# Processor.net
KiCad netlist of a schematic drawn in Altium Designer
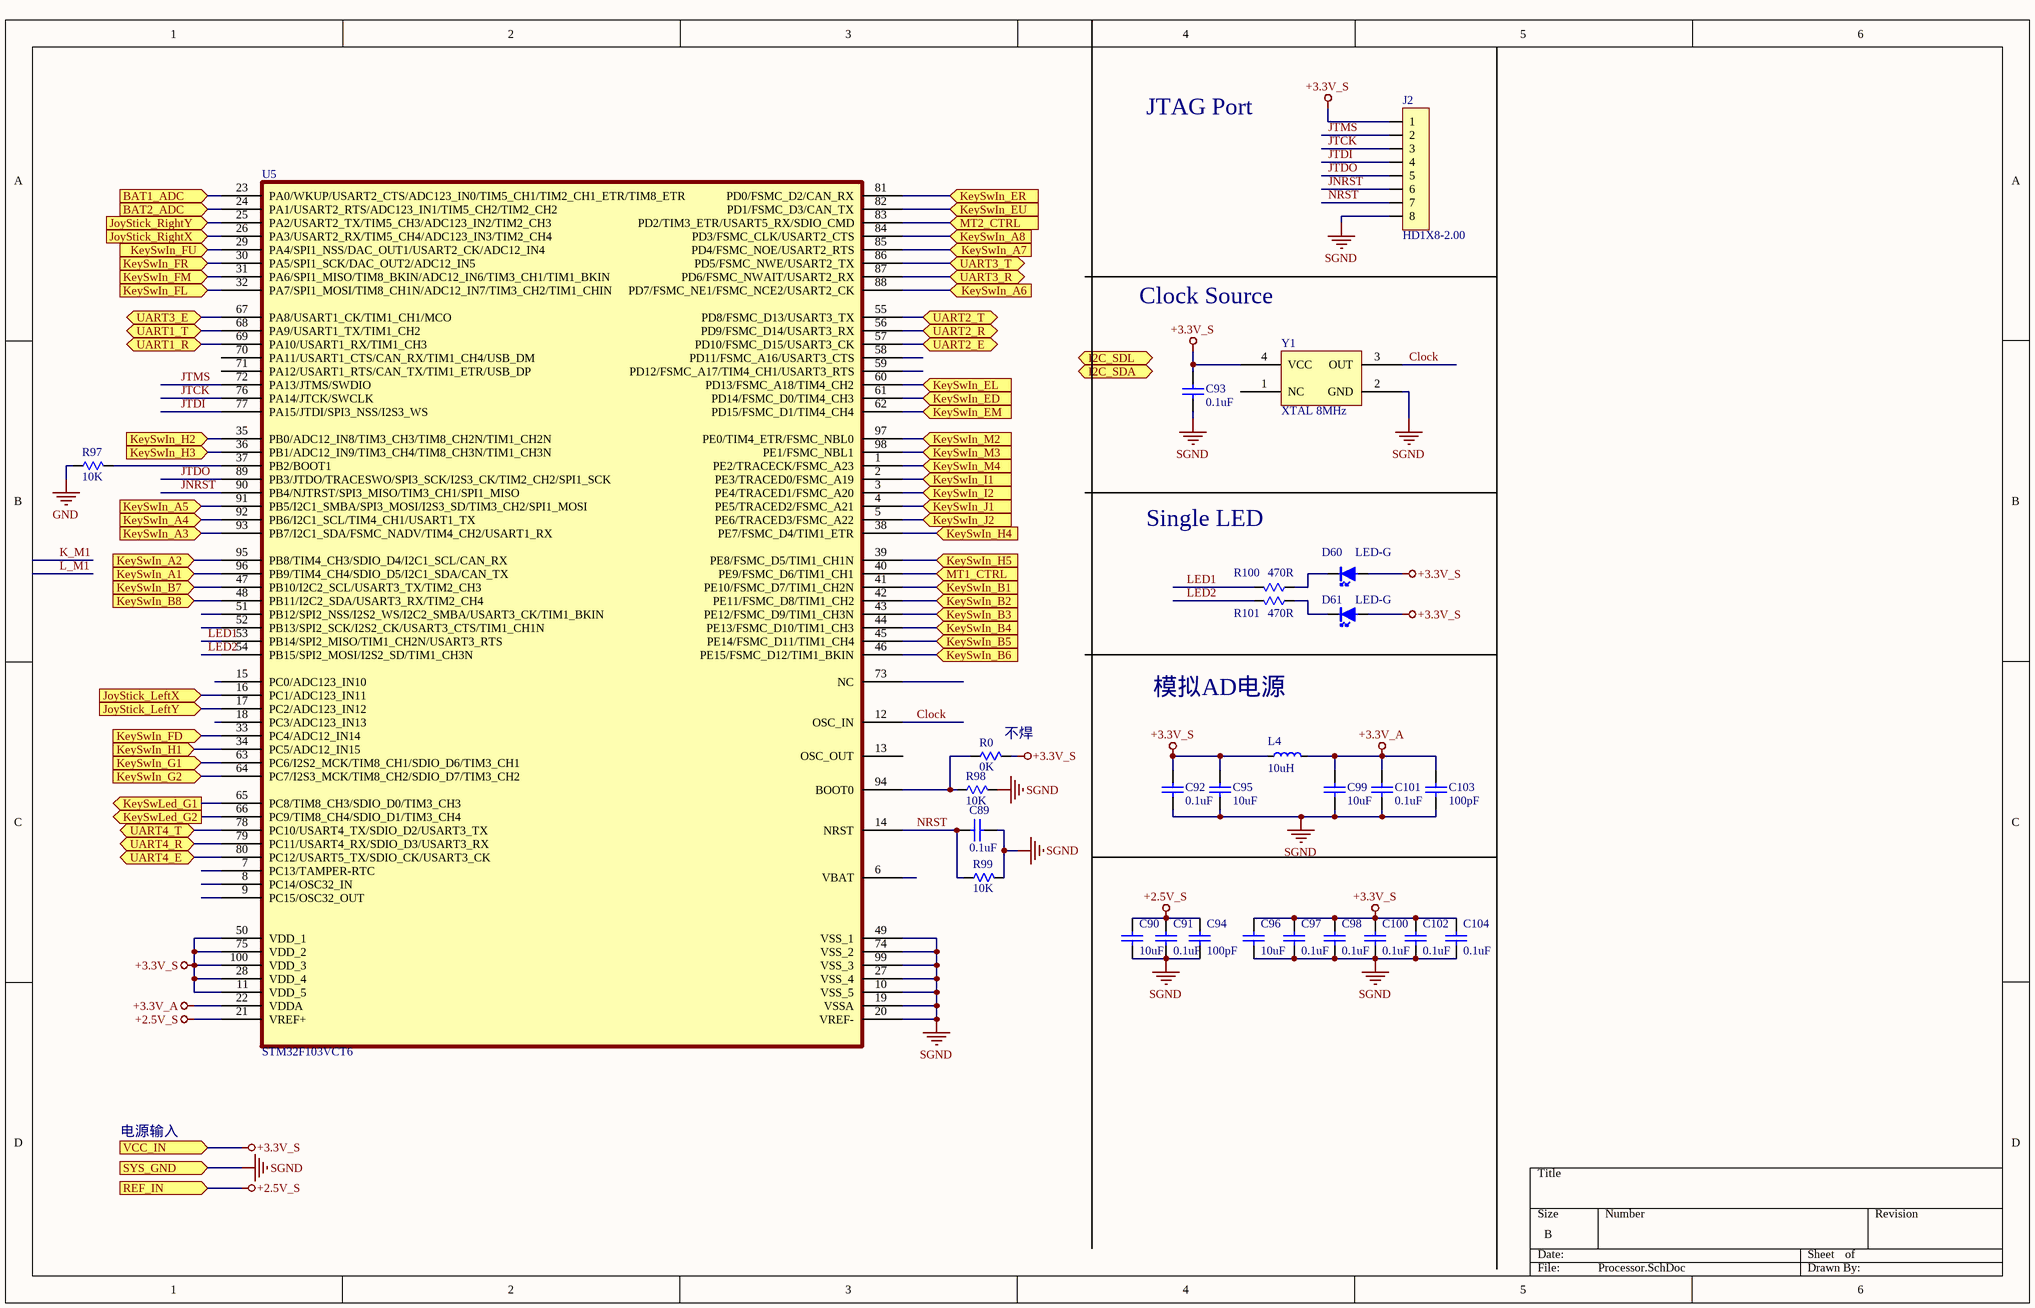
[diagram p0: Processor.SchDoc]

(export (version "E")
  (design (tool "Eeschema 10.0.6"))
  (components
    (comp (ref "C89")
      (value "0.1uF")
      (footprint "C0603")
      (description "CAP")
      (fields (field (name "PUBLISHER") "Altium Limited"))
      (libsource (lib "Passive Components Class") (part "CAP"))
    )
    (comp (ref "C90")
      (value "10uF")
      (footprint "C0805")
      (description "CAP")
      (fields (field (name "PUBLISHER") "Altium Limited"))
      (libsource (lib "Passive Components Class") (part "CAP"))
    )
    (comp (ref "C91")
      (value "0.1uF")
      (footprint "C0603")
      (description "CAP")
      (fields (field (name "PUBLISHER") "Altium Limited"))
      (libsource (lib "Passive Components Class") (part "CAP"))
    )
    (comp (ref "C92")
      (value "0.1uF")
      (footprint "C0603")
      (description "CAP")
      (fields (field (name "PUBLISHER") "Altium Limited"))
      (libsource (lib "Passive Components Class") (part "CAP"))
    )
    (comp (ref "C93")
      (value "0.1uF")
      (footprint "C0603")
      (description "Capacitor")
      (fields (field (name "PUBLISHER") "Altium Limited"))
      (libsource (lib "Miscellaneous Devices") (part "Cap"))
    )
    (comp (ref "C94")
      (value "100pF")
      (footprint "C0603")
      (description "CAP")
      (fields (field (name "PUBLISHER") "Altium Limited"))
      (libsource (lib "Passive Components Class") (part "CAP"))
    )
    (comp (ref "C95")
      (value "10uF")
      (footprint "C0805")
      (description "CAP")
      (fields (field (name "PUBLISHER") "Altium Limited"))
      (libsource (lib "Passive Components Class") (part "CAP"))
    )
    (comp (ref "C96")
      (value "10uF")
      (footprint "C0805")
      (description "CAP")
      (fields (field (name "PUBLISHER") "Altium Limited"))
      (libsource (lib "Passive Components Class") (part "CAP"))
    )
    (comp (ref "C97")
      (value "0.1uF")
      (footprint "C0603")
      (description "CAP")
      (fields (field (name "PUBLISHER") "Altium Limited"))
      (libsource (lib "Passive Components Class") (part "CAP"))
    )
    (comp (ref "C98")
      (value "0.1uF")
      (footprint "C0603")
      (description "CAP")
      (fields (field (name "PUBLISHER") "Altium Limited"))
      (libsource (lib "Passive Components Class") (part "CAP"))
    )
    (comp (ref "C99")
      (value "10uF")
      (footprint "C0805")
      (description "CAP")
      (fields (field (name "PUBLISHER") "Altium Limited"))
      (libsource (lib "Passive Components Class") (part "CAP"))
    )
    (comp (ref "C100")
      (value "0.1uF")
      (footprint "C0603")
      (description "CAP")
      (fields (field (name "PUBLISHER") "Altium Limited"))
      (libsource (lib "Passive Components Class") (part "CAP"))
    )
    (comp (ref "C101")
      (value "0.1uF")
      (footprint "C0603")
      (description "CAP")
      (fields (field (name "PUBLISHER") "Altium Limited"))
      (libsource (lib "Passive Components Class") (part "CAP"))
    )
    (comp (ref "C102")
      (value "0.1uF")
      (footprint "C0603")
      (description "CAP")
      (fields (field (name "PUBLISHER") "Altium Limited"))
      (libsource (lib "Passive Components Class") (part "CAP"))
    )
    (comp (ref "C103")
      (value "100pF")
      (footprint "C0603")
      (description "CAP")
      (fields (field (name "PUBLISHER") "Altium Limited"))
      (libsource (lib "Passive Components Class") (part "CAP"))
    )
    (comp (ref "C104")
      (value "0.1uF")
      (footprint "C0603")
      (description "CAP")
      (fields (field (name "PUBLISHER") "Altium Limited"))
      (libsource (lib "Passive Components Class") (part "CAP"))
    )
    (comp (ref "D60")
      (value "LED-G")
      (footprint "LED0805")
      (libsource (lib "Passive Components Class") (part "LED"))
    )
    (comp (ref "D61")
      (value "LED-G")
      (footprint "LED0805")
      (libsource (lib "Passive Components Class") (part "LED"))
    )
    (comp (ref "J2")
      (value "HD1X8-2.00")
      (footprint "SHD1X8-2.00")
      (libsource (lib "Connector Class") (part "HEADER1X8"))
    )
    (comp (ref "L4")
      (value "10uH")
      (footprint "L0603-C")
      (description "INDUCTOR")
      (fields (field (name "PUBLISHER") "Altium Limited"))
      (libsource (lib "Passive Components Class") (part "INDUCTOR"))
    )
    (comp (ref "R0")
      (value "0K")
      (footprint "R0603")
      (description "Resistor")
      (fields (field (name "PUBLISHER") "Altium Limited"))
      (libsource (lib "UP-Robot") (part "Res"))
    )
    (comp (ref "R97")
      (value "10K")
      (footprint "R0603")
      (description "Resistor")
      (fields (field (name "PUBLISHER") "Altium Limited"))
      (libsource (lib "UP-Robot") (part "Res"))
    )
    (comp (ref "R98")
      (value "10K")
      (footprint "R0603")
      (description "Resistor")
      (fields (field (name "PUBLISHER") "Altium Limited"))
      (libsource (lib "UP-Robot") (part "Res"))
    )
    (comp (ref "R99")
      (value "10K")
      (footprint "R0603")
      (description "Resistor")
      (fields (field (name "PUBLISHER") "Altium Limited"))
      (libsource (lib "UP-Robot") (part "Res"))
    )
    (comp (ref "R100")
      (value "470R")
      (footprint "R0805")
      (description "Resistor")
      (fields (field (name "PUBLISHER") "Altium Limited"))
      (libsource (lib "UP-Robot") (part "Res"))
    )
    (comp (ref "R101")
      (value "470R")
      (footprint "R0805")
      (description "Resistor")
      (fields (field (name "PUBLISHER") "Altium Limited"))
      (libsource (lib "UP-Robot") (part "Res"))
    )
    (comp (ref "U5")
      (value "STM32F103VCT6")
      (footprint "STM32F103VCT6")
      (libsource (lib "Microcontrollers Class") (part "STM32F103VCT6"))
    )
    (comp (ref "Y1")
      (value "XTAL 8MHz")
      (footprint "XTAL 5.0X7.0-SM")
      (libsource (lib "Mic2805") (part "XTAL"))
    )
  )
  (nets
    (net (code "1") (name "+2.5V_S") (class "Default")
      (node (ref "C90") (pin "1") (pinfunction "1_1") (pintype "passive"))
      (node (ref "C91") (pin "1") (pinfunction "1_1") (pintype "passive"))
      (node (ref "C94") (pin "1") (pinfunction "1_1") (pintype "passive"))
      (node (ref "U5") (pin "21") (pinfunction "VREF+_21") (pintype "passive"))
    )
    (net (code "2") (name "+3.3V_A") (class "Default")
      (node (ref "C101") (pin "2") (pinfunction "2_2") (pintype "passive"))
      (node (ref "C103") (pin "2") (pinfunction "2_2") (pintype "passive"))
      (node (ref "C99") (pin "2") (pinfunction "2_2") (pintype "passive"))
      (node (ref "L4") (pin "2") (pinfunction "2_2") (pintype "passive"))
      (node (ref "U5") (pin "22") (pinfunction "VDDA_22") (pintype "passive"))
    )
    (net (code "3") (name "+3.3V_S") (class "Default")
      (node (ref "C100") (pin "1") (pinfunction "1_1") (pintype "passive"))
      (node (ref "C102") (pin "1") (pinfunction "1_1") (pintype "passive"))
      (node (ref "C104") (pin "1") (pinfunction "1_1") (pintype "passive"))
      (node (ref "C92") (pin "2") (pinfunction "2_2") (pintype "passive"))
      (node (ref "C93") (pin "2") (pinfunction "2_2") (pintype "passive"))
      (node (ref "C95") (pin "2") (pinfunction "2_2") (pintype "passive"))
      (node (ref "C96") (pin "1") (pinfunction "1_1") (pintype "passive"))
      (node (ref "C97") (pin "1") (pinfunction "1_1") (pintype "passive"))
      (node (ref "C98") (pin "1") (pinfunction "1_1") (pintype "passive"))
      (node (ref "D60") (pin "1") (pinfunction "A_1") (pintype "passive"))
      (node (ref "D61") (pin "1") (pinfunction "A_1") (pintype "passive"))
      (node (ref "J2") (pin "1") (pinfunction "1_1") (pintype "passive"))
      (node (ref "L4") (pin "1") (pinfunction "1_1") (pintype "passive"))
      (node (ref "R0") (pin "1") (pinfunction "1_1") (pintype "passive"))
      (node (ref "U5") (pin "100") (pinfunction "VDD_3_100") (pintype "passive"))
      (node (ref "U5") (pin "11") (pinfunction "VDD_5_11") (pintype "passive"))
      (node (ref "U5") (pin "28") (pinfunction "VDD_4_28") (pintype "passive"))
      (node (ref "U5") (pin "50") (pinfunction "VDD_1_50") (pintype "passive"))
      (node (ref "U5") (pin "75") (pinfunction "VDD_2_75") (pintype "passive"))
      (node (ref "Y1") (pin "4") (pinfunction "VCC_4") (pintype "passive"))
    )
    (net (code "4") (name "/BAT1_ADC") (class "Default")
      (node (ref "U5") (pin "23") (pinfunction "PA0/WKUP/USART2_CTS/ADC123_IN0/TIM5_CH1/TIM2_CH1_ETR/TIM8_ETR_23") (pintype "passive"))
    )
    (net (code "5") (name "/BAT2_ADC") (class "Default")
      (node (ref "U5") (pin "24") (pinfunction "PA1/USART2_RTS/ADC123_IN1/TIM5_CH2/TIM2_CH2_24") (pintype "passive"))
    )
    (net (code "6") (name "/Clock") (class "Default")
      (node (ref "U5") (pin "12") (pinfunction "OSC_IN_12") (pintype "passive"))
      (node (ref "Y1") (pin "3") (pinfunction "OUT_3") (pintype "passive"))
    )
    (net (code "9") (name "/JNRST") (class "Default")
      (node (ref "J2") (pin "6") (pinfunction "6_6") (pintype "passive"))
      (node (ref "U5") (pin "90") (pinfunction "PB4/NJTRST/SPI3_MISO/TIM3_CH1/SPI1_MISO_90") (pintype "passive"))
    )
    (net (code "10") (name "/JTCK") (class "Default")
      (node (ref "J2") (pin "3") (pinfunction "3_3") (pintype "passive"))
      (node (ref "U5") (pin "76") (pinfunction "PA14/JTCK/SWCLK_76") (pintype "passive"))
    )
    (net (code "11") (name "/JTDI") (class "Default")
      (node (ref "J2") (pin "4") (pinfunction "4_4") (pintype "passive"))
      (node (ref "U5") (pin "77") (pinfunction "PA15/JTDI/SPI3_NSS/I2S3_WS_77") (pintype "passive"))
    )
    (net (code "12") (name "/JTDO") (class "Default")
      (node (ref "J2") (pin "5") (pinfunction "5_5") (pintype "passive"))
      (node (ref "U5") (pin "89") (pinfunction "PB3/JTDO/TRACESWO/SPI3_SCK/I2S3_CK/TIM2_CH2/SPI1_SCK_89") (pintype "passive"))
    )
    (net (code "13") (name "/JTMS") (class "Default")
      (node (ref "J2") (pin "2") (pinfunction "2_2") (pintype "passive"))
      (node (ref "U5") (pin "72") (pinfunction "PA13/JTMS/SWDIO_72") (pintype "passive"))
    )
    (net (code "14") (name "/JoyStick_LeftX") (class "Default")
      (node (ref "U5") (pin "16") (pinfunction "PC1/ADC123_IN11_16") (pintype "passive"))
    )
    (net (code "15") (name "/JoyStick_LeftY") (class "Default")
      (node (ref "U5") (pin "17") (pinfunction "PC2/ADC123_IN12_17") (pintype "passive"))
    )
    (net (code "16") (name "/JoyStick_RightX") (class "Default")
      (node (ref "U5") (pin "26") (pinfunction "PA3/USART2_RX/TIM5_CH4/ADC123_IN3/TIM2_CH4_26") (pintype "passive"))
    )
    (net (code "17") (name "/JoyStick_RightY") (class "Default")
      (node (ref "U5") (pin "25") (pinfunction "PA2/USART2_TX/TIM5_CH3/ADC123_IN2/TIM2_CH3_25") (pintype "passive"))
    )
    (net (code "19") (name "/KeySwIn_A1") (class "Default")
      (node (ref "U5") (pin "96") (pinfunction "PB9/TIM4_CH4/SDIO_D5/I2C1_SDA/CAN_TX_96") (pintype "passive"))
    )
    (net (code "20") (name "/KeySwIn_A2") (class "Default")
      (node (ref "U5") (pin "95") (pinfunction "PB8/TIM4_CH3/SDIO_D4/I2C1_SCL/CAN_RX_95") (pintype "passive"))
    )
    (net (code "21") (name "/KeySwIn_A3") (class "Default")
      (node (ref "U5") (pin "93") (pinfunction "PB7/I2C1_SDA/FSMC_NADV/TIM4_CH2/USART1_RX_93") (pintype "passive"))
    )
    (net (code "22") (name "/KeySwIn_A4") (class "Default")
      (node (ref "U5") (pin "92") (pinfunction "PB6/I2C1_SCL/TIM4_CH1/USART1_TX_92") (pintype "passive"))
    )
    (net (code "23") (name "/KeySwIn_A5") (class "Default")
      (node (ref "U5") (pin "91") (pinfunction "PB5/I2C1_SMBA/SPI3_MOSI/I2S3_SD/TIM3_CH2/SPI1_MOSI_91") (pintype "passive"))
    )
    (net (code "24") (name "/KeySwIn_A6") (class "Default")
      (node (ref "U5") (pin "88") (pinfunction "PD7/FSMC_NE1/FSMC_NCE2/USART2_CK_88") (pintype "passive"))
    )
    (net (code "25") (name "/KeySwIn_A7") (class "Default")
      (node (ref "U5") (pin "85") (pinfunction "PD4/FSMC_NOE/USART2_RTS_85") (pintype "passive"))
    )
    (net (code "26") (name "/KeySwIn_A8") (class "Default")
      (node (ref "U5") (pin "84") (pinfunction "PD3/FSMC_CLK/USART2_CTS_84") (pintype "passive"))
    )
    (net (code "27") (name "/KeySwIn_B1") (class "Default")
      (node (ref "U5") (pin "41") (pinfunction "PE10/FSMC_D7/TIM1_CH2N_41") (pintype "passive"))
    )
    (net (code "28") (name "/KeySwIn_B2") (class "Default")
      (node (ref "U5") (pin "42") (pinfunction "PE11/FSMC_D8/TIM1_CH2_42") (pintype "passive"))
    )
    (net (code "29") (name "/KeySwIn_B3") (class "Default")
      (node (ref "U5") (pin "43") (pinfunction "PE12/FSMC_D9/TIM1_CH3N_43") (pintype "passive"))
    )
    (net (code "30") (name "/KeySwIn_B4") (class "Default")
      (node (ref "U5") (pin "44") (pinfunction "PE13/FSMC_D10/TIM1_CH3_44") (pintype "passive"))
    )
    (net (code "31") (name "/KeySwIn_B5") (class "Default")
      (node (ref "U5") (pin "45") (pinfunction "PE14/FSMC_D11/TIM1_CH4_45") (pintype "passive"))
    )
    (net (code "32") (name "/KeySwIn_B6") (class "Default")
      (node (ref "U5") (pin "46") (pinfunction "PE15/FSMC_D12/TIM1_BKIN_46") (pintype "passive"))
    )
    (net (code "33") (name "/KeySwIn_B7") (class "Default")
      (node (ref "U5") (pin "47") (pinfunction "PB10/I2C2_SCL/USART3_TX/TIM2_CH3_47") (pintype "passive"))
    )
    (net (code "34") (name "/KeySwIn_B8") (class "Default")
      (node (ref "U5") (pin "48") (pinfunction "PB11/I2C2_SDA/USART3_RX/TIM2_CH4_48") (pintype "passive"))
    )
    (net (code "35") (name "/KeySwIn_ED") (class "Default")
      (node (ref "U5") (pin "61") (pinfunction "PD14/FSMC_D0/TIM4_CH3_61") (pintype "passive"))
    )
    (net (code "36") (name "/KeySwIn_EL") (class "Default")
      (node (ref "U5") (pin "60") (pinfunction "PD13/FSMC_A18/TIM4_CH2_60") (pintype "passive"))
    )
    (net (code "37") (name "/KeySwIn_EM") (class "Default")
      (node (ref "U5") (pin "62") (pinfunction "PD15/FSMC_D1/TIM4_CH4_62") (pintype "passive"))
    )
    (net (code "38") (name "/KeySwIn_ER") (class "Default")
      (node (ref "U5") (pin "81") (pinfunction "PD0/FSMC_D2/CAN_RX_81") (pintype "passive"))
    )
    (net (code "39") (name "/KeySwIn_EU") (class "Default")
      (node (ref "U5") (pin "82") (pinfunction "PD1/FSMC_D3/CAN_TX_82") (pintype "passive"))
    )
    (net (code "40") (name "/KeySwIn_FD") (class "Default")
      (node (ref "U5") (pin "33") (pinfunction "PC4/ADC12_IN14_33") (pintype "passive"))
    )
    (net (code "41") (name "/KeySwIn_FL") (class "Default")
      (node (ref "U5") (pin "32") (pinfunction "PA7/SPI1_MOSI/TIM8_CH1N/ADC12_IN7/TIM3_CH2/TIM1_CHIN_32") (pintype "passive"))
    )
    (net (code "42") (name "/KeySwIn_FM") (class "Default")
      (node (ref "U5") (pin "31") (pinfunction "PA6/SPI1_MISO/TIM8_BKIN/ADC12_IN6/TIM3_CH1/TIM1_BKIN_31") (pintype "passive"))
    )
    (net (code "43") (name "/KeySwIn_FR") (class "Default")
      (node (ref "U5") (pin "30") (pinfunction "PA5/SPI1_SCK/DAC_OUT2/ADC12_IN5_30") (pintype "passive"))
    )
    (net (code "44") (name "/KeySwIn_FU") (class "Default")
      (node (ref "U5") (pin "29") (pinfunction "PA4/SPI1_NSS/DAC_OUT1/USART2_CK/ADC12_IN4_29") (pintype "passive"))
    )
    (net (code "45") (name "/KeySwIn_G1") (class "Default")
      (node (ref "U5") (pin "63") (pinfunction "PC6/I2S2_MCK/TIM8_CH1/SDIO_D6/TIM3_CH1_63") (pintype "passive"))
    )
    (net (code "46") (name "/KeySwIn_G2") (class "Default")
      (node (ref "U5") (pin "64") (pinfunction "PC7/I2S3_MCK/TIM8_CH2/SDIO_D7/TIM3_CH2_64") (pintype "passive"))
    )
    (net (code "47") (name "/KeySwIn_H1") (class "Default")
      (node (ref "U5") (pin "34") (pinfunction "PC5/ADC12_IN15_34") (pintype "passive"))
    )
    (net (code "48") (name "/KeySwIn_H2") (class "Default")
      (node (ref "U5") (pin "35") (pinfunction "PB0/ADC12_IN8/TIM3_CH3/TIM8_CH2N/TIM1_CH2N_35") (pintype "passive"))
    )
    (net (code "49") (name "/KeySwIn_H3") (class "Default")
      (node (ref "U5") (pin "36") (pinfunction "PB1/ADC12_IN9/TIM3_CH4/TIM8_CH3N/TIM1_CH3N_36") (pintype "passive"))
    )
    (net (code "50") (name "/KeySwIn_H4") (class "Default")
      (node (ref "U5") (pin "38") (pinfunction "PE7/FSMC_D4/TIM1_ETR_38") (pintype "passive"))
    )
    (net (code "51") (name "/KeySwIn_H5") (class "Default")
      (node (ref "U5") (pin "39") (pinfunction "PE8/FSMC_D5/TIM1_CH1N_39") (pintype "passive"))
    )
    (net (code "52") (name "/KeySwIn_I1") (class "Default")
      (node (ref "U5") (pin "2") (pinfunction "PE3/TRACED0/FSMC_A19_2") (pintype "passive"))
    )
    (net (code "53") (name "/KeySwIn_I2") (class "Default")
      (node (ref "U5") (pin "3") (pinfunction "PE4/TRACED1/FSMC_A20_3") (pintype "passive"))
    )
    (net (code "54") (name "/KeySwIn_J1") (class "Default")
      (node (ref "U5") (pin "4") (pinfunction "PE5/TRACED2/FSMC_A21_4") (pintype "passive"))
    )
    (net (code "55") (name "/KeySwIn_J2") (class "Default")
      (node (ref "U5") (pin "5") (pinfunction "PE6/TRACED3/FSMC_A22_5") (pintype "passive"))
    )
    (net (code "56") (name "/KeySwIn_M2") (class "Default")
      (node (ref "U5") (pin "97") (pinfunction "PE0/TIM4_ETR/FSMC_NBL0_97") (pintype "passive"))
    )
    (net (code "57") (name "/KeySwIn_M3") (class "Default")
      (node (ref "U5") (pin "98") (pinfunction "PE1/FSMC_NBL1_98") (pintype "passive"))
    )
    (net (code "58") (name "/KeySwIn_M4") (class "Default")
      (node (ref "U5") (pin "1") (pinfunction "PE2/TRACECK/FSMC_A23_1") (pintype "passive"))
    )
    (net (code "59") (name "/KeySwLed_G1") (class "Default")
      (node (ref "U5") (pin "65") (pinfunction "PC8/TIM8_CH3/SDIO_D0/TIM3_CH3_65") (pintype "passive"))
    )
    (net (code "60") (name "/KeySwLed_G2") (class "Default")
      (node (ref "U5") (pin "66") (pinfunction "PC9/TIM8_CH4/SDIO_D1/TIM3_CH4_66") (pintype "passive"))
    )
    (net (code "61") (name "/LED1") (class "Default")
      (node (ref "R100") (pin "1") (pinfunction "1_1") (pintype "passive"))
      (node (ref "U5") (pin "53") (pinfunction "PB14/SPI2_MISO/TIM1_CH2N/USART3_RTS_53") (pintype "passive"))
    )
    (net (code "62") (name "/LED2") (class "Default")
      (node (ref "R101") (pin "1") (pinfunction "1_1") (pintype "passive"))
      (node (ref "U5") (pin "54") (pinfunction "PB15/SPI2_MOSI/I2S2_SD/TIM1_CH3N_54") (pintype "passive"))
    )
    (net (code "64") (name "/MT1_CTRL") (class "Default")
      (node (ref "U5") (pin "40") (pinfunction "PE9/FSMC_D6/TIM1_CH1_40") (pintype "passive"))
    )
    (net (code "65") (name "/MT2_CTRL") (class "Default")
      (node (ref "U5") (pin "83") (pinfunction "PD2/TIM3_ETR/USART5_RX/SDIO_CMD_83") (pintype "passive"))
    )
    (net (code "66") (name "/NRST") (class "Default")
      (node (ref "C89") (pin "1") (pinfunction "1_1") (pintype "passive"))
      (node (ref "J2") (pin "7") (pinfunction "7_7") (pintype "passive"))
      (node (ref "R99") (pin "2") (pinfunction "2_2") (pintype "passive"))
      (node (ref "U5") (pin "14") (pinfunction "NRST_14") (pintype "passive"))
    )
    (net (code "67") (name "/UART1_R") (class "Default")
      (node (ref "U5") (pin "69") (pinfunction "PA10/USART1_RX/TIM1_CH3_69") (pintype "passive"))
    )
    (net (code "68") (name "/UART1_T") (class "Default")
      (node (ref "U5") (pin "68") (pinfunction "PA9/USART1_TX/TIM1_CH2_68") (pintype "passive"))
    )
    (net (code "69") (name "/UART2_E") (class "Default")
      (node (ref "U5") (pin "57") (pinfunction "PD10/FSMC_D15/USART3_CK_57") (pintype "passive"))
    )
    (net (code "70") (name "/UART2_R") (class "Default")
      (node (ref "U5") (pin "56") (pinfunction "PD9/FSMC_D14/USART3_RX_56") (pintype "passive"))
    )
    (net (code "71") (name "/UART2_T") (class "Default")
      (node (ref "U5") (pin "55") (pinfunction "PD8/FSMC_D13/USART3_TX_55") (pintype "passive"))
    )
    (net (code "72") (name "/UART3_E") (class "Default")
      (node (ref "U5") (pin "67") (pinfunction "PA8/USART1_CK/TIM1_CH1/MCO_67") (pintype "passive"))
    )
    (net (code "73") (name "/UART3_R") (class "Default")
      (node (ref "U5") (pin "87") (pinfunction "PD6/FSMC_NWAIT/USART2_RX_87") (pintype "passive"))
    )
    (net (code "74") (name "/UART3_T") (class "Default")
      (node (ref "U5") (pin "86") (pinfunction "PD5/FSMC_NWE/USART2_TX_86") (pintype "passive"))
    )
    (net (code "75") (name "/UART4_E") (class "Default")
      (node (ref "U5") (pin "80") (pinfunction "PC12/USART5_TX/SDIO_CK/USART3_CK_80") (pintype "passive"))
    )
    (net (code "76") (name "/UART4_R") (class "Default")
      (node (ref "U5") (pin "79") (pinfunction "PC11/USART4_RX/SDIO_D3/USART3_RX_79") (pintype "passive"))
    )
    (net (code "77") (name "/UART4_T") (class "Default")
      (node (ref "U5") (pin "78") (pinfunction "PC10/USART4_TX/SDIO_D2/USART3_TX_78") (pintype "passive"))
    )
    (net (code "78") (name "GND") (class "Default")
      (node (ref "R97") (pin "2") (pinfunction "2_2") (pintype "passive"))
    )
    (net (code "79") (name "Net-(D60-K)") (class "Default")
      (node (ref "D60") (pin "2") (pinfunction "K_2") (pintype "passive"))
      (node (ref "R100") (pin "2") (pinfunction "2_2") (pintype "passive"))
    )
    (net (code "80") (name "Net-(D61-K)") (class "Default")
      (node (ref "D61") (pin "2") (pinfunction "K_2") (pintype "passive"))
      (node (ref "R101") (pin "2") (pinfunction "2_2") (pintype "passive"))
    )
    (net (code "81") (name "Net-(U5-BOOT0)") (class "Default")
      (node (ref "R0") (pin "2") (pinfunction "2_2") (pintype "passive"))
      (node (ref "R98") (pin "2") (pinfunction "2_2") (pintype "passive"))
      (node (ref "U5") (pin "94") (pinfunction "BOOT0_94") (pintype "passive"))
    )
    (net (code "82") (name "Net-(U5-PB2{slash}BOOT1)") (class "Default")
      (node (ref "R97") (pin "1") (pinfunction "1_1") (pintype "passive"))
      (node (ref "U5") (pin "37") (pinfunction "PB2/BOOT1_37") (pintype "passive"))
    )
    (net (code "83") (name "SGND") (class "Default")
      (node (ref "C100") (pin "2") (pinfunction "2_2") (pintype "passive"))
      (node (ref "C101") (pin "1") (pinfunction "1_1") (pintype "passive"))
      (node (ref "C102") (pin "2") (pinfunction "2_2") (pintype "passive"))
      (node (ref "C103") (pin "1") (pinfunction "1_1") (pintype "passive"))
      (node (ref "C104") (pin "2") (pinfunction "2_2") (pintype "passive"))
      (node (ref "C89") (pin "2") (pinfunction "2_2") (pintype "passive"))
      (node (ref "C90") (pin "2") (pinfunction "2_2") (pintype "passive"))
      (node (ref "C91") (pin "2") (pinfunction "2_2") (pintype "passive"))
      (node (ref "C92") (pin "1") (pinfunction "1_1") (pintype "passive"))
      (node (ref "C93") (pin "1") (pinfunction "1_1") (pintype "passive"))
      (node (ref "C94") (pin "2") (pinfunction "2_2") (pintype "passive"))
      (node (ref "C95") (pin "1") (pinfunction "1_1") (pintype "passive"))
      (node (ref "C96") (pin "2") (pinfunction "2_2") (pintype "passive"))
      (node (ref "C97") (pin "2") (pinfunction "2_2") (pintype "passive"))
      (node (ref "C98") (pin "2") (pinfunction "2_2") (pintype "passive"))
      (node (ref "C99") (pin "1") (pinfunction "1_1") (pintype "passive"))
      (node (ref "J2") (pin "8") (pinfunction "8_8") (pintype "passive"))
      (node (ref "R98") (pin "1") (pinfunction "1_1") (pintype "passive"))
      (node (ref "R99") (pin "1") (pinfunction "1_1") (pintype "passive"))
      (node (ref "U5") (pin "10") (pinfunction "VSS_5_10") (pintype "passive"))
      (node (ref "U5") (pin "19") (pinfunction "VSSA_19") (pintype "passive"))
      (node (ref "U5") (pin "20") (pinfunction "VREF-_20") (pintype "passive"))
      (node (ref "U5") (pin "27") (pinfunction "VSS_4_27") (pintype "passive"))
      (node (ref "U5") (pin "49") (pinfunction "VSS_1_49") (pintype "passive"))
      (node (ref "U5") (pin "74") (pinfunction "VSS_2_74") (pintype "passive"))
      (node (ref "U5") (pin "99") (pinfunction "VSS_3_99") (pintype "passive"))
      (node (ref "Y1") (pin "2") (pinfunction "GND_2") (pintype "passive"))
    )
    (net (code "84") (name "unconnected-(U5-NC-Pad73)") (class "Default")
      (node (ref "U5") (pin "73") (pinfunction "NC_73") (pintype "passive"))
    )
    (net (code "85") (name "unconnected-(U5-OSC_OUT-Pad13)") (class "Default")
      (node (ref "U5") (pin "13") (pinfunction "OSC_OUT_13") (pintype "passive"))
    )
    (net (code "86") (name "unconnected-(U5-PA11{slash}USART1_CTS{slash}CAN_RX{slash}TIM1_CH4{slash}USB_DM-Pad70)") (class "Default")
      (node (ref "U5") (pin "70") (pinfunction "PA11/USART1_CTS/CAN_RX/TIM1_CH4/USB_DM_70") (pintype "passive"))
    )
    (net (code "87") (name "unconnected-(U5-PA12{slash}USART1_RTS{slash}CAN_TX{slash}TIM1_ETR{slash}USB_DP-Pad71)") (class "Default")
      (node (ref "U5") (pin "71") (pinfunction "PA12/USART1_RTS/CAN_TX/TIM1_ETR/USB_DP_71") (pintype "passive"))
    )
    (net (code "88") (name "unconnected-(U5-PB12{slash}SPI2_NSS{slash}I2S2_WS{slash}I2C2_SMBA{slash}USART3_CK{slash}TIM1_BKIN-Pad51)") (class "Default")
      (node (ref "U5") (pin "51") (pinfunction "PB12/SPI2_NSS/I2S2_WS/I2C2_SMBA/USART3_CK/TIM1_BKIN_51") (pintype "passive"))
    )
    (net (code "89") (name "unconnected-(U5-PB13{slash}SPI2_SCK{slash}I2S2_CK{slash}USART3_CTS{slash}TIM1_CH1N-Pad52)") (class "Default")
      (node (ref "U5") (pin "52") (pinfunction "PB13/SPI2_SCK/I2S2_CK/USART3_CTS/TIM1_CH1N_52") (pintype "passive"))
    )
    (net (code "90") (name "unconnected-(U5-PC0{slash}ADC123_IN10-Pad15)") (class "Default")
      (node (ref "U5") (pin "15") (pinfunction "PC0/ADC123_IN10_15") (pintype "passive"))
    )
    (net (code "91") (name "unconnected-(U5-PC3{slash}ADC123_IN13-Pad18)") (class "Default")
      (node (ref "U5") (pin "18") (pinfunction "PC3/ADC123_IN13_18") (pintype "passive"))
    )
    (net (code "92") (name "unconnected-(U5-PC13{slash}TAMPER-RTC-Pad7)") (class "Default")
      (node (ref "U5") (pin "7") (pinfunction "PC13/TAMPER-RTC_7") (pintype "passive"))
    )
    (net (code "93") (name "unconnected-(U5-PC14{slash}OSC32_IN-Pad8)") (class "Default")
      (node (ref "U5") (pin "8") (pinfunction "PC14/OSC32_IN_8") (pintype "passive"))
    )
    (net (code "94") (name "unconnected-(U5-PC15{slash}OSC32_OUT-Pad9)") (class "Default")
      (node (ref "U5") (pin "9") (pinfunction "PC15/OSC32_OUT_9") (pintype "passive"))
    )
    (net (code "95") (name "unconnected-(U5-PD11{slash}FSMC_A16{slash}USART3_CTS-Pad58)") (class "Default")
      (node (ref "U5") (pin "58") (pinfunction "PD11/FSMC_A16/USART3_CTS_58") (pintype "passive"))
    )
    (net (code "96") (name "unconnected-(U5-PD12{slash}FSMC_A17{slash}TIM4_CH1{slash}USART3_RTS-Pad59)") (class "Default")
      (node (ref "U5") (pin "59") (pinfunction "PD12/FSMC_A17/TIM4_CH1/USART3_RTS_59") (pintype "passive"))
    )
    (net (code "97") (name "unconnected-(U5-VBAT-Pad6)") (class "Default")
      (node (ref "U5") (pin "6") (pinfunction "VBAT_6") (pintype "passive"))
    )
    (net (code "98") (name "unconnected-(Y1-NC-Pad1)") (class "Default")
      (node (ref "Y1") (pin "1") (pinfunction "NC_1") (pintype "passive"))
    )
  )
)
